# AKS.net
KiCad netlist of a schematic drawn in Altium Designer
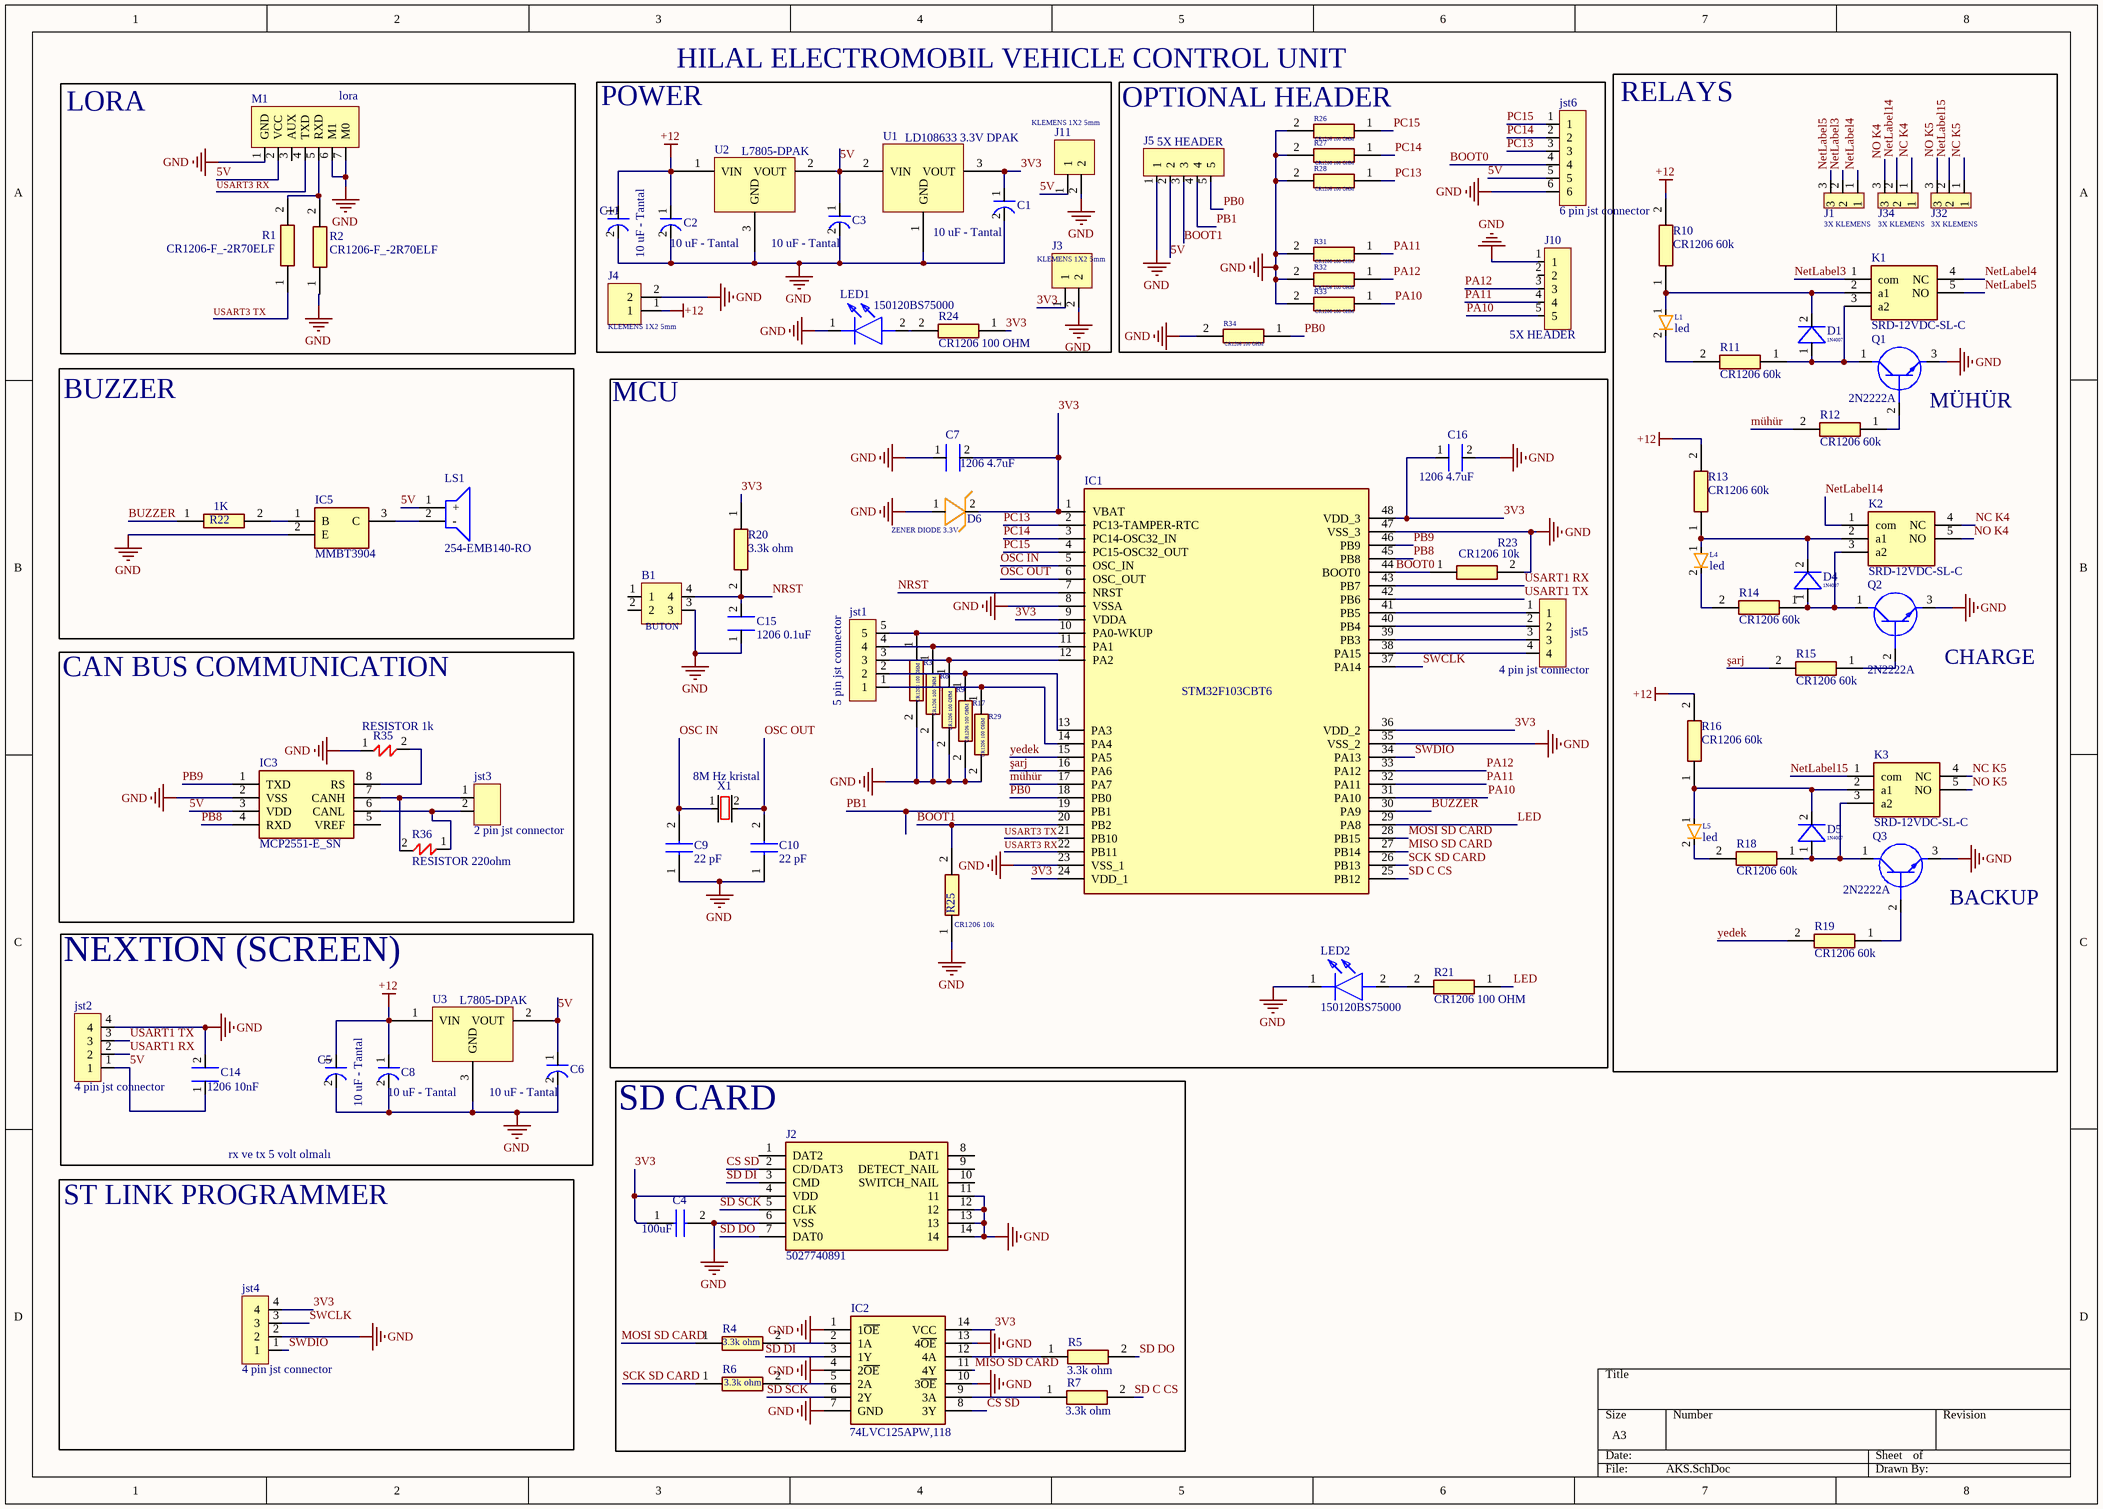
[diagram p0: AKS.SchDoc]

(export (version "E")
  (design (tool "Eeschema 10.0.6"))
  (components
    (comp (ref "B1") (value "BUTON") (footprint "BUTON") (libsource (lib "Schlib1") (part "BUTON")))
    (comp (ref "C1")
      (value "10 uF - Tantal")
      (footprint "C1206-TANT")
      (libsource (lib "Schlib1") (part "10 uF - Tantal"))
    )
    (comp (ref "C2")
      (value "10 uF - Tantal")
      (footprint "C1206-TANT")
      (libsource (lib "Schlib1") (part "10 uF - Tantal"))
    )
    (comp (ref "C3")
      (value "10 uF - Tantal")
      (footprint "C1206-TANT")
      (libsource (lib "Schlib1") (part "10 uF - Tantal"))
    )
    (comp (ref "C4")
      (value "100uF")
      (footprint "PcbLib1:CAPC2012X94N")
      (description "Capacitor")
      (fields
        (field (name "MANUFACTURER_PART_NUMBER") "08055A150JAT2A")
        (field (name "MOUSER PART NUMBER") "581-08055A150J")
      )
      (libsource (lib "*") (part "08055A150JAT2A"))
    )
    (comp (ref "C5")
      (value "10 uF - Tantal")
      (footprint "C1206-TANT")
      (libsource (lib "Schlib1") (part "10 uF - Tantal"))
    )
    (comp (ref "C6")
      (value "10 uF - Tantal")
      (footprint "C1206-TANT")
      (libsource (lib "Schlib1") (part "10 uF - Tantal"))
    )
    (comp (ref "C7")
      (value "1206 4.7uF")
      (footprint "C1206")
      (description "10 uF C1206")
      (libsource (lib "Schlib1") (part "10 uF C1206"))
    )
    (comp (ref "C8")
      (value "10 uF - Tantal")
      (footprint "C1206-TANT")
      (libsource (lib "Schlib1") (part "10 uF - Tantal"))
    )
    (comp (ref "C9")
      (value "22 pF")
      (footprint "PcbLib1:CAPC2012X94N")
      (description "Capacitor")
      (fields
        (field (name "MANUFACTURER_PART_NUMBER") "08055A150JAT2A")
        (field (name "MOUSER PART NUMBER") "581-08055A150J")
      )
      (libsource (lib "*") (part "08055A150JAT2A"))
    )
    (comp (ref "C10")
      (value "22 pF")
      (footprint "PcbLib1:CAPC2012X94N")
      (description "Capacitor")
      (fields
        (field (name "MANUFACTURER_PART_NUMBER") "08055A150JAT2A")
        (field (name "MOUSER PART NUMBER") "581-08055A150J")
      )
      (libsource (lib "*") (part "08055A150JAT2A"))
    )
    (comp (ref "C11")
      (value "10 uF - Tantal")
      (footprint "C1206-TANT")
      (libsource (lib "Schlib1") (part "10 uF - Tantal"))
    )
    (comp (ref "C14")
      (value "1206 10nF")
      (footprint "C1206")
      (description "10 uF C1206")
      (libsource (lib "Schlib1") (part "10 uF C1206"))
    )
    (comp (ref "C15")
      (value "1206 0.1uF")
      (footprint "C1206")
      (description "10 uF C1206")
      (libsource (lib "Schlib1") (part "10 uF C1206"))
    )
    (comp (ref "C16")
      (value "1206 4.7uF")
      (footprint "C1206")
      (description "10 uF C1206")
      (libsource (lib "Schlib1") (part "10 uF C1206"))
    )
    (comp (ref "D1")
      (value "1N4007")
      (footprint "SF-26 DIODE")
      (description "DIODE")
      (libsource (lib "Schlib1") (part "SF-26 DIODE"))
    )
    (comp (ref "D4")
      (value "1N4007")
      (footprint "SF-26 DIODE")
      (description "DIODE")
      (libsource (lib "Schlib1") (part "SF-26 DIODE"))
    )
    (comp (ref "D5")
      (value "1N4007")
      (footprint "SF-26 DIODE")
      (description "DIODE")
      (libsource (lib "Schlib1") (part "SF-26 DIODE"))
    )
    (comp (ref "D6")
      (value "ZENER DIODE 3.3V")
      (footprint "3.3 VOLT ZENER")
      (description "ZENER DIODE")
      (libsource (lib "Schlib1") (part "ZENER DIODE 3.3V"))
    )
    (comp (ref "IC1")
      (value "STM32F103CBT6")
      (footprint "PcbLib1:QFP50P900X900X160-48N")
      (description "Integrated Circuit")
      (fields (field (name "MOUSER PART NUMBER") "511-STM32F103CBT6"))
      (libsource (lib "Schlib1") (part "STM32F103CBT6"))
    )
    (comp (ref "IC2")
      (value "74LVC125APW,118")
      (footprint "PcbLib1:SOP65P640X110-14N")
      (description "Integrated Circuit")
      (fields (field (name "MOUSER PART NUMBER") "771-74LVC125APW-T"))
      (libsource (lib "*") (part "74LVC125APW,118"))
    )
    (comp (ref "IC3")
      (value "MCP2551-E_SN")
      (footprint "PcbLib1:SOIC127P600X175-8N")
      (description "Integrated Circuit")
      (fields
        (field (name "MANUFACTURER_PART_NUMBER") "MCP2551-E/SN")
        (field (name "MOUSER PART NUMBER") "579-MCP2551-E/SN")
      )
      (libsource (lib "Schlib1") (part "MCP2551-E_SN"))
    )
    (comp (ref "IC5")
      (value "MMBT3904")
      (footprint "PcbLib1:SOT95P240X120-3N")
      (description "Integrated Circuit")
      (fields (field (name "MOUSER PART NUMBER") "637-MMBT3904"))
      (libsource (lib "*") (part "MMBT3904"))
    )
    (comp (ref "J1")
      (value "3X KLEMENS")
      (footprint "3x klemens 5mm")
      (libsource (lib "Schlib1") (part "3X KLEMENS"))
    )
    (comp (ref "J2")
      (value "5027740891")
      (footprint "PcbLib1:5027740891")
      (description "Connector")
      (libsource (lib "*") (part "5027740891"))
    )
    (comp (ref "J3")
      (value "KLEMENS 1X2 5mm")
      (footprint "KLEMENS 1x2 - 5mm")
      (description "KLEMENS")
      (libsource (lib "Schlib1") (part "KLEMENS 1X2 3.5mm"))
    )
    (comp (ref "J4")
      (value "KLEMENS 1X2 5mm")
      (footprint "KLEMENS 1x2 - 5mm")
      (description "KLEMENS")
      (libsource (lib "") (part "KLEMENS 1X2 3.5mm_1"))
    )
    (comp (ref "J5") (value "5X HEADER") (footprint "5X HEADER") (libsource (lib "") (part "5X HEADER_1")))
    (comp (ref "J10")
      (value "5X HEADER")
      (footprint "5X HEADER")
      (libsource (lib "Schlib1") (part "5X HEADER"))
    )
    (comp (ref "J11")
      (value "KLEMENS 1X2 5mm")
      (footprint "KLEMENS 1x2 - 5mm")
      (description "KLEMENS")
      (libsource (lib "Schlib1") (part "KLEMENS 1X2 3.5mm"))
    )
    (comp (ref "J32")
      (value "3X KLEMENS")
      (footprint "3x klemens 5mm")
      (libsource (lib "Schlib1") (part "3X KLEMENS"))
    )
    (comp (ref "J34")
      (value "3X KLEMENS")
      (footprint "3x klemens 5mm")
      (libsource (lib "Schlib1") (part "3X KLEMENS"))
    )
    (comp (ref "jst1")
      (value "5 pin jst connector")
      (footprint "5 pin jst")
      (libsource (lib "Schlib1") (part "5 pin jst connector"))
    )
    (comp (ref "jst2")
      (value "4 pin jst connector")
      (footprint "4pin-jst")
      (libsource (lib "") (part "4 pin jst connector_1"))
    )
    (comp (ref "jst3")
      (value "2 pin jst connector")
      (footprint "2 pin jst connector")
      (libsource (lib "Schlib1") (part "2 pin jst connector"))
    )
    (comp (ref "jst4")
      (value "4 pin jst connector")
      (footprint "4pin-jst")
      (libsource (lib "") (part "4 pin jst connector_1"))
    )
    (comp (ref "jst5")
      (value "4 pin jst connector")
      (footprint "4pin-jst")
      (libsource (lib "Schlib1") (part "4 pin jst connector"))
    )
    (comp (ref "jst6")
      (value "6 pin jst connector")
      (footprint "6 pin jst connecttor")
      (description "connector")
      (libsource (lib "Schlib1") (part "6 pin jst connector"))
    )
    (comp (ref "K1")
      (value "SRD-12VDC-SL-C")
      (footprint "RELAY")
      (description "Relay or Contactor")
      (libsource (lib "Schlib1") (part "SRD-12VDC-SL-C"))
    )
    (comp (ref "K2")
      (value "SRD-12VDC-SL-C")
      (footprint "RELAY")
      (description "Relay or Contactor")
      (libsource (lib "Schlib1") (part "SRD-12VDC-SL-C"))
    )
    (comp (ref "K3")
      (value "SRD-12VDC-SL-C")
      (footprint "RELAY")
      (description "Relay or Contactor")
      (libsource (lib "Schlib1") (part "SRD-12VDC-SL-C"))
    )
    (comp (ref "L1") (value "led") (footprint "led") (libsource (lib "Schlib1") (part "led")))
    (comp (ref "L4") (value "led") (footprint "led") (libsource (lib "Schlib1") (part "led")))
    (comp (ref "L5") (value "led") (footprint "led") (libsource (lib "Schlib1") (part "led")))
    (comp (ref "LED1")
      (value "150120BS75000")
      (footprint "PcbLib1:LEDC3214X78N")
      (description "LED")
      (fields (field (name "MOUSER PART NUMBER") "710-150120BS75000"))
      (libsource (lib "Schlib1") (part "150120BS75000"))
    )
    (comp (ref "LED2")
      (value "150120BS75000")
      (footprint "PcbLib1:LEDC3214X78N")
      (description "LED")
      (fields (field (name "MOUSER PART NUMBER") "710-150120BS75000"))
      (libsource (lib "Schlib1") (part "150120BS75000"))
    )
    (comp (ref "LS1")
      (value "254-EMB140-RO")
      (footprint "PcbLib1:254EMB140RO")
      (description "Loudspeaker or Buzzer")
      (libsource (lib "*") (part "254-EMB140-RO"))
    )
    (comp (ref "M1") (value "lora") (footprint "LORA") (libsource (lib "Schlib1") (part "lora")))
    (comp (ref "Q1")
      (value "2N2222A")
      (footprint "PcbLib1:2N2222A")
      (description "Transistor BJT NPN")
      (libsource (lib "Schlib1") (part "2N2222A"))
    )
    (comp (ref "Q2")
      (value "2N2222A")
      (footprint "PcbLib1:2N2222A")
      (description "Transistor BJT NPN")
      (libsource (lib "Schlib1") (part "2N2222A"))
    )
    (comp (ref "Q3")
      (value "2N2222A")
      (footprint "PcbLib1:2N2222A")
      (description "Transistor BJT NPN")
      (libsource (lib "Schlib1") (part "2N2222A"))
    )
    (comp (ref "R1")
      (value "CR1206-F_-2R70ELF")
      (footprint "PcbLib1:RESC3216X75N")
      (description "Resistor")
      (fields
        (field (name "MANUFACTURER_PART_NUMBER") "CR1206-F/-2R70ELF")
        (field (name "MOUSER PART NUMBER") "652-CR1206-F/2R70ELF")
      )
      (libsource (lib "Schlib1") (part "CR1206-F_-2R70ELF"))
    )
    (comp (ref "R2")
      (value "CR1206-F_-2R70ELF")
      (footprint "PcbLib1:RESC3216X75N")
      (description "Resistor")
      (fields
        (field (name "MANUFACTURER_PART_NUMBER") "CR1206-F/-2R70ELF")
        (field (name "MOUSER PART NUMBER") "652-CR1206-F/2R70ELF")
      )
      (libsource (lib "Schlib1") (part "CR1206-F_-2R70ELF"))
    )
    (comp (ref "R3")
      (value "CR1206 100 OHM")
      (footprint "PcbLib1:RESC3216X75N")
      (description "Resistor")
      (fields
        (field (name "MANUFACTURER_PART_NUMBER") "CR1206-F/-2R70ELF")
        (field (name "MOUSER PART NUMBER") "652-CR1206-F/2R70ELF")
      )
      (libsource (lib "") (part "CR1206-F_-2R70ELF_1"))
    )
    (comp (ref "R4")
      (value "3.3k ohm")
      (footprint "PcbLib1:RESC2012X65N")
      (description "Resistor")
      (fields
        (field (name "MANUFACTURER_PART_NUMBER") "CPF0805B100RE1")
        (field (name "MOUSER PART NUMBER") "279-CPF0805B100RE1")
      )
      (libsource (lib "*") (part "CPF0805B100RE1"))
    )
    (comp (ref "R5")
      (value "3.3k ohm")
      (footprint "PcbLib1:RESC2012X65N")
      (description "Resistor")
      (fields
        (field (name "MANUFACTURER_PART_NUMBER") "CPF0805B100RE1")
        (field (name "MOUSER PART NUMBER") "279-CPF0805B100RE1")
      )
      (libsource (lib "*") (part "CPF0805B100RE1"))
    )
    (comp (ref "R6")
      (value "3.3k ohm")
      (footprint "PcbLib1:RESC2012X65N")
      (description "Resistor")
      (fields
        (field (name "MANUFACTURER_PART_NUMBER") "CPF0805B100RE1")
        (field (name "MOUSER PART NUMBER") "279-CPF0805B100RE1")
      )
      (libsource (lib "*") (part "CPF0805B100RE1"))
    )
    (comp (ref "R7")
      (value "3.3k ohm")
      (footprint "PcbLib1:RESC2012X65N")
      (description "Resistor")
      (fields
        (field (name "MANUFACTURER_PART_NUMBER") "CPF0805B100RE1")
        (field (name "MOUSER PART NUMBER") "279-CPF0805B100RE1")
      )
      (libsource (lib "*") (part "CPF0805B100RE1"))
    )
    (comp (ref "R8")
      (value "CR1206 100 OHM")
      (footprint "PcbLib1:RESC3216X75N")
      (description "Resistor")
      (fields
        (field (name "MANUFACTURER_PART_NUMBER") "CR1206-F/-2R70ELF")
        (field (name "MOUSER PART NUMBER") "652-CR1206-F/2R70ELF")
      )
      (libsource (lib "") (part "CR1206-F_-2R70ELF_1"))
    )
    (comp (ref "R9")
      (value "CR1206 100 OHM")
      (footprint "PcbLib1:RESC3216X75N")
      (description "Resistor")
      (fields
        (field (name "MANUFACTURER_PART_NUMBER") "CR1206-F/-2R70ELF")
        (field (name "MOUSER PART NUMBER") "652-CR1206-F/2R70ELF")
      )
      (libsource (lib "") (part "CR1206-F_-2R70ELF_1"))
    )
    (comp (ref "R10")
      (value "CR1206 60k")
      (footprint "PcbLib1:RESC3216X75N")
      (description "Resistor")
      (fields
        (field (name "MANUFACTURER_PART_NUMBER") "CR1206-F/-2R70ELF")
        (field (name "MOUSER PART NUMBER") "652-CR1206-F/2R70ELF")
      )
      (libsource (lib "") (part "CR1206-F_-2R70ELF_2"))
    )
    (comp (ref "R11")
      (value "CR1206 60k")
      (footprint "PcbLib1:RESC3216X75N")
      (description "Resistor")
      (fields
        (field (name "MANUFACTURER_PART_NUMBER") "CR1206-F/-2R70ELF")
        (field (name "MOUSER PART NUMBER") "652-CR1206-F/2R70ELF")
      )
      (libsource (lib "*") (part "CR1206-F_-2R70ELF"))
    )
    (comp (ref "R12")
      (value "CR1206 60k")
      (footprint "PcbLib1:RESC3216X75N")
      (description "Resistor")
      (fields
        (field (name "MANUFACTURER_PART_NUMBER") "CR1206-F/-2R70ELF")
        (field (name "MOUSER PART NUMBER") "652-CR1206-F/2R70ELF")
      )
      (libsource (lib "*") (part "CR1206-F_-2R70ELF"))
    )
    (comp (ref "R13")
      (value "CR1206 60k")
      (footprint "PcbLib1:RESC3216X75N")
      (description "Resistor")
      (fields
        (field (name "MANUFACTURER_PART_NUMBER") "CR1206-F/-2R70ELF")
        (field (name "MOUSER PART NUMBER") "652-CR1206-F/2R70ELF")
      )
      (libsource (lib "") (part "CR1206-F_-2R70ELF_2"))
    )
    (comp (ref "R14")
      (value "CR1206 60k")
      (footprint "PcbLib1:RESC3216X75N")
      (description "Resistor")
      (fields
        (field (name "MANUFACTURER_PART_NUMBER") "CR1206-F/-2R70ELF")
        (field (name "MOUSER PART NUMBER") "652-CR1206-F/2R70ELF")
      )
      (libsource (lib "*") (part "CR1206-F_-2R70ELF"))
    )
    (comp (ref "R15")
      (value "CR1206 60k")
      (footprint "PcbLib1:RESC3216X75N")
      (description "Resistor")
      (fields
        (field (name "MANUFACTURER_PART_NUMBER") "CR1206-F/-2R70ELF")
        (field (name "MOUSER PART NUMBER") "652-CR1206-F/2R70ELF")
      )
      (libsource (lib "*") (part "CR1206-F_-2R70ELF"))
    )
    (comp (ref "R16")
      (value "CR1206 60k")
      (footprint "PcbLib1:RESC3216X75N")
      (description "Resistor")
      (fields
        (field (name "MANUFACTURER_PART_NUMBER") "CR1206-F/-2R70ELF")
        (field (name "MOUSER PART NUMBER") "652-CR1206-F/2R70ELF")
      )
      (libsource (lib "") (part "CR1206-F_-2R70ELF_2"))
    )
    (comp (ref "R17")
      (value "CR1206 100 OHM")
      (footprint "PcbLib1:RESC3216X75N")
      (description "Resistor")
      (fields
        (field (name "MANUFACTURER_PART_NUMBER") "CR1206-F/-2R70ELF")
        (field (name "MOUSER PART NUMBER") "652-CR1206-F/2R70ELF")
      )
      (libsource (lib "") (part "CR1206-F_-2R70ELF_1"))
    )
    (comp (ref "R18")
      (value "CR1206 60k")
      (footprint "PcbLib1:RESC3216X75N")
      (description "Resistor")
      (fields
        (field (name "MANUFACTURER_PART_NUMBER") "CR1206-F/-2R70ELF")
        (field (name "MOUSER PART NUMBER") "652-CR1206-F/2R70ELF")
      )
      (libsource (lib "*") (part "CR1206-F_-2R70ELF"))
    )
    (comp (ref "R19")
      (value "CR1206 60k")
      (footprint "PcbLib1:RESC3216X75N")
      (description "Resistor")
      (fields
        (field (name "MANUFACTURER_PART_NUMBER") "CR1206-F/-2R70ELF")
        (field (name "MOUSER PART NUMBER") "652-CR1206-F/2R70ELF")
      )
      (libsource (lib "*") (part "CR1206-F_-2R70ELF"))
    )
    (comp (ref "R20")
      (value "3.3k ohm")
      (footprint "PcbLib1:RESC2012X65N")
      (description "Resistor")
      (fields
        (field (name "MANUFACTURER_PART_NUMBER") "CPF0805B100RE1")
        (field (name "MOUSER PART NUMBER") "279-CPF0805B100RE1")
      )
      (libsource (lib "") (part "CPF0805B100RE1_1"))
    )
    (comp (ref "R21")
      (value "CR1206 100 OHM")
      (footprint "PcbLib1:RESC3216X75N")
      (description "Resistor")
      (fields
        (field (name "MANUFACTURER_PART_NUMBER") "CR1206-F/-2R70ELF")
        (field (name "MOUSER PART NUMBER") "652-CR1206-F/2R70ELF")
      )
      (libsource (lib "*") (part "CR1206-F_-2R70ELF"))
    )
    (comp (ref "R22")
      (value "1K")
      (footprint "PcbLib1:RESC2012X65N")
      (description "Resistor")
      (fields
        (field (name "MANUFACTURER_PART_NUMBER") "CPF0805B100RE1")
        (field (name "MOUSER PART NUMBER") "279-CPF0805B100RE1")
      )
      (libsource (lib "*") (part "CPF0805B100RE1"))
    )
    (comp (ref "R23")
      (value "CR1206 10k")
      (footprint "PcbLib1:RESC3216X75N")
      (description "Resistor")
      (fields
        (field (name "MANUFACTURER_PART_NUMBER") "CR1206-F/-2R70ELF")
        (field (name "MOUSER PART NUMBER") "652-CR1206-F/2R70ELF")
      )
      (libsource (lib "") (part "CR1206-F_-2R70ELF_3"))
    )
    (comp (ref "R24")
      (value "CR1206 100 OHM")
      (footprint "PcbLib1:RESC3216X75N")
      (description "Resistor")
      (fields
        (field (name "MANUFACTURER_PART_NUMBER") "CR1206-F/-2R70ELF")
        (field (name "MOUSER PART NUMBER") "652-CR1206-F/2R70ELF")
      )
      (libsource (lib "*") (part "CR1206-F_-2R70ELF"))
    )
    (comp (ref "R25")
      (value "CR1206 10k")
      (footprint "PcbLib1:RESC3216X75N")
      (description "Resistor")
      (fields
        (field (name "MANUFACTURER_PART_NUMBER") "CR1206-F/-2R70ELF")
        (field (name "MOUSER PART NUMBER") "652-CR1206-F/2R70ELF")
      )
      (libsource (lib "") (part "CR1206-F_-2R70ELF_2"))
    )
    (comp (ref "R26")
      (value "CR1206 100 OHM")
      (footprint "PcbLib1:RESC3216X75N")
      (description "Resistor")
      (fields
        (field (name "MANUFACTURER_PART_NUMBER") "CR1206-F/-2R70ELF")
        (field (name "MOUSER PART NUMBER") "652-CR1206-F/2R70ELF")
      )
      (libsource (lib "*") (part "CR1206-F_-2R70ELF"))
    )
    (comp (ref "R27")
      (value "CR1206 100 OHM")
      (footprint "PcbLib1:RESC3216X75N")
      (description "Resistor")
      (fields
        (field (name "MANUFACTURER_PART_NUMBER") "CR1206-F/-2R70ELF")
        (field (name "MOUSER PART NUMBER") "652-CR1206-F/2R70ELF")
      )
      (libsource (lib "*") (part "CR1206-F_-2R70ELF"))
    )
    (comp (ref "R28")
      (value "CR1206 100 OHM")
      (footprint "PcbLib1:RESC3216X75N")
      (description "Resistor")
      (fields
        (field (name "MANUFACTURER_PART_NUMBER") "CR1206-F/-2R70ELF")
        (field (name "MOUSER PART NUMBER") "652-CR1206-F/2R70ELF")
      )
      (libsource (lib "*") (part "CR1206-F_-2R70ELF"))
    )
    (comp (ref "R29")
      (value "CR1206 100 OHM")
      (footprint "PcbLib1:RESC3216X75N")
      (description "Resistor")
      (fields
        (field (name "MANUFACTURER_PART_NUMBER") "CR1206-F/-2R70ELF")
        (field (name "MOUSER PART NUMBER") "652-CR1206-F/2R70ELF")
      )
      (libsource (lib "") (part "CR1206-F_-2R70ELF_1"))
    )
    (comp (ref "R31")
      (value "CR1206 100 OHM")
      (footprint "PcbLib1:RESC3216X75N")
      (description "Resistor")
      (fields
        (field (name "MANUFACTURER_PART_NUMBER") "CR1206-F/-2R70ELF")
        (field (name "MOUSER PART NUMBER") "652-CR1206-F/2R70ELF")
      )
      (libsource (lib "*") (part "CR1206-F_-2R70ELF"))
    )
    (comp (ref "R32")
      (value "CR1206 100 OHM")
      (footprint "PcbLib1:RESC3216X75N")
      (description "Resistor")
      (fields
        (field (name "MANUFACTURER_PART_NUMBER") "CR1206-F/-2R70ELF")
        (field (name "MOUSER PART NUMBER") "652-CR1206-F/2R70ELF")
      )
      (libsource (lib "*") (part "CR1206-F_-2R70ELF"))
    )
    (comp (ref "R33")
      (value "CR1206 100 OHM")
      (footprint "PcbLib1:RESC3216X75N")
      (description "Resistor")
      (fields
        (field (name "MANUFACTURER_PART_NUMBER") "CR1206-F/-2R70ELF")
        (field (name "MOUSER PART NUMBER") "652-CR1206-F/2R70ELF")
      )
      (libsource (lib "*") (part "CR1206-F_-2R70ELF"))
    )
    (comp (ref "R34")
      (value "CR1206 100 OHM")
      (footprint "PcbLib1:RESC3216X75N")
      (description "Resistor")
      (fields
        (field (name "MANUFACTURER_PART_NUMBER") "CR1206-F/-2R70ELF")
        (field (name "MOUSER PART NUMBER") "652-CR1206-F/2R70ELF")
      )
      (libsource (lib "*") (part "CR1206-F_-2R70ELF"))
    )
    (comp (ref "R35")
      (value "RESISTOR 1k")
      (footprint "GENERAL RESISTOR")
      (description "GENERAL TYPE THT RES")
      (libsource (lib "Schlib1") (part "RESISTOR"))
    )
    (comp (ref "R36")
      (value "RESISTOR 220ohm")
      (footprint "GENERAL RESISTOR")
      (description "GENERAL TYPE THT RES")
      (libsource (lib "Schlib1") (part "RESISTOR"))
    )
    (comp (ref "U1")
      (value "LD108633 3.3V DPAK")
      (footprint "DPAK228P972X240-3N")
      (description "LD108633 3.3V REGULATOR")
      (libsource (lib "Schlib1") (part "LD108633 3.3V DPAK"))
    )
    (comp (ref "U2")
      (value "L7805-DPAK")
      (footprint "DPAK228P972X240-3N")
      (description "L7805 5V REGULATOR. SMD PAKET")
      (libsource (lib "Schlib1") (part "L7805-DPAK"))
    )
    (comp (ref "U3")
      (value "L7805-DPAK")
      (footprint "DPAK228P972X240-3N")
      (description "L7805 5V REGULATOR. SMD PAKET")
      (libsource (lib "Schlib1") (part "L7805-DPAK"))
    )
    (comp (ref "X1")
      (value "8M Hz kristal")
      (footprint "8M Hz kristal")
      (libsource (lib "Schlib1") (part "8M Hz kristal"))
    )
  )
  (nets
    (net (code "1") (name "+12") (class "Default")
      (node (ref "C11") (pin "1") (pinfunction "1_1") (pintype "passive"))
      (node (ref "C2") (pin "1") (pinfunction "1_1") (pintype "passive"))
      (node (ref "C5") (pin "1") (pinfunction "1_1") (pintype "passive"))
      (node (ref "C8") (pin "1") (pinfunction "1_1") (pintype "passive"))
      (node (ref "J4") (pin "1") (pinfunction "1_1") (pintype "passive"))
      (node (ref "R10") (pin "2") (pinfunction "2_2") (pintype "passive"))
      (node (ref "R13") (pin "2") (pinfunction "2_2") (pintype "passive"))
      (node (ref "R16") (pin "2") (pinfunction "2_2") (pintype "passive"))
      (node (ref "U2") (pin "1") (pinfunction "VIN_1") (pintype "passive"))
      (node (ref "U3") (pin "1") (pinfunction "VIN_1") (pintype "passive"))
    )
    (net (code "2") (name "/3V3") (class "Default")
      (node (ref "C1") (pin "1") (pinfunction "1_1") (pintype "passive"))
      (node (ref "C16") (pin "1") (pinfunction "1_1") (pintype "passive"))
      (node (ref "C4") (pin "1") (pinfunction "1_1") (pintype "passive"))
      (node (ref "C7") (pin "2") (pinfunction "2_2") (pintype "passive"))
      (node (ref "D6") (pin "2") (pinfunction "2_2") (pintype "passive"))
      (node (ref "IC1") (pin "1") (pinfunction "VBAT_1") (pintype "passive"))
      (node (ref "IC1") (pin "24") (pinfunction "VDD_1_24") (pintype "passive"))
      (node (ref "IC1") (pin "36") (pinfunction "VDD_2_36") (pintype "passive"))
      (node (ref "IC1") (pin "48") (pinfunction "VDD_3_48") (pintype "passive"))
      (node (ref "IC1") (pin "9") (pinfunction "VDDA_9") (pintype "passive"))
      (node (ref "IC2") (pin "14") (pinfunction "VCC_14") (pintype "passive"))
      (node (ref "J2") (pin "4") (pinfunction "VDD_4") (pintype "passive"))
      (node (ref "J3") (pin "1") (pinfunction "1_1") (pintype "passive"))
      (node (ref "R20") (pin "1") (pinfunction "1_1") (pintype "passive"))
      (node (ref "R24") (pin "1") (pinfunction "1_1") (pintype "passive"))
      (node (ref "U1") (pin "3") (pinfunction "VOUT_3") (pintype "passive"))
      (node (ref "jst4") (pin "4") (pinfunction "4_4") (pintype "passive"))
    )
    (net (code "3") (name "/5V") (class "Default")
      (node (ref "C14") (pin "1") (pinfunction "1_1") (pintype "passive"))
      (node (ref "C3") (pin "1") (pinfunction "1_1") (pintype "passive"))
      (node (ref "C6") (pin "1") (pinfunction "1_1") (pintype "passive"))
      (node (ref "IC3") (pin "3") (pinfunction "VDD_3") (pintype "passive"))
      (node (ref "J11") (pin "1") (pinfunction "1_1") (pintype "passive"))
      (node (ref "J5") (pin "2") (pinfunction "2_2") (pintype "passive"))
      (node (ref "LS1") (pin "1") (pinfunction "+_1") (pintype "passive"))
      (node (ref "M1") (pin "2") (pinfunction "VCC_2") (pintype "passive"))
      (node (ref "U1") (pin "2") (pinfunction "VIN_2") (pintype "passive"))
      (node (ref "U2") (pin "2") (pinfunction "VOUT_2") (pintype "passive"))
      (node (ref "U3") (pin "2") (pinfunction "VOUT_2") (pintype "passive"))
      (node (ref "jst2") (pin "1") (pinfunction "1_1") (pintype "passive"))
      (node (ref "jst6") (pin "5") (pinfunction "5_5") (pintype "passive"))
    )
    (net (code "4") (name "/BOOT0") (class "Default")
      (node (ref "IC1") (pin "44") (pinfunction "BOOT0_44") (pintype "passive"))
      (node (ref "R23") (pin "1") (pinfunction "1_1") (pintype "passive"))
      (node (ref "jst6") (pin "4") (pinfunction "4_4") (pintype "passive"))
    )
    (net (code "5") (name "/BOOT1") (class "Default")
      (node (ref "IC1") (pin "20") (pinfunction "PB2_20") (pintype "passive"))
      (node (ref "J5") (pin "3") (pinfunction "3_3") (pintype "passive"))
      (node (ref "R25") (pin "2") (pinfunction "2_2") (pintype "passive"))
    )
    (net (code "6") (name "/BUZZER") (class "Default")
      (node (ref "IC1") (pin "30") (pinfunction "PA9_30") (pintype "passive"))
      (node (ref "R22") (pin "1") (pinfunction "1_1") (pintype "passive"))
    )
    (net (code "7") (name "/CS SD") (class "Default")
      (node (ref "IC2") (pin "8") (pinfunction "3Y_8") (pintype "passive"))
      (node (ref "J2") (pin "2") (pinfunction "CD/DAT3_2") (pintype "passive"))
    )
    (net (code "8") (name "/LED") (class "Default")
      (node (ref "IC1") (pin "29") (pinfunction "PA8_29") (pintype "passive"))
      (node (ref "R21") (pin "1") (pinfunction "1_1") (pintype "passive"))
    )
    (net (code "9") (name "/MISO SD CARD") (class "Default")
      (node (ref "IC1") (pin "27") (pinfunction "PB14_27") (pintype "passive"))
      (node (ref "IC2") (pin "11") (pinfunction "4Y_11") (pintype "passive"))
    )
    (net (code "10") (name "/MOSI SD CARD") (class "Default")
      (node (ref "IC1") (pin "28") (pinfunction "PB15_28") (pintype "passive"))
      (node (ref "R4") (pin "1") (pinfunction "1_1") (pintype "passive"))
    )
    (net (code "11") (name "/NC K4") (class "Default")
      (node (ref "J34") (pin "1") (pinfunction "1_1") (pintype "passive"))
      (node (ref "K2") (pin "4") (pinfunction "NC_4") (pintype "passive"))
    )
    (net (code "12") (name "/NC K5") (class "Default")
      (node (ref "J32") (pin "1") (pinfunction "1_1") (pintype "passive"))
      (node (ref "K3") (pin "4") (pinfunction "NC_4") (pintype "passive"))
    )
    (net (code "13") (name "/NO K4") (class "Default")
      (node (ref "J34") (pin "3") (pinfunction "3_3") (pintype "passive"))
      (node (ref "K2") (pin "5") (pinfunction "NO_5") (pintype "passive"))
    )
    (net (code "14") (name "/NO K5") (class "Default")
      (node (ref "J32") (pin "3") (pinfunction "3_3") (pintype "passive"))
      (node (ref "K3") (pin "5") (pinfunction "NO_5") (pintype "passive"))
    )
    (net (code "15") (name "/NRST") (class "Default")
      (node (ref "B1") (pin "4") (pinfunction "4_4") (pintype "passive"))
      (node (ref "C15") (pin "2") (pinfunction "2_2") (pintype "passive"))
      (node (ref "IC1") (pin "7") (pinfunction "NRST_7") (pintype "passive"))
      (node (ref "R20") (pin "2") (pinfunction "2_2") (pintype "passive"))
    )
    (net (code "16") (name "/NetLabel3") (class "Default")
      (node (ref "J1") (pin "2") (pinfunction "2_2") (pintype "passive"))
      (node (ref "K1") (pin "1") (pinfunction "com_1") (pintype "passive"))
    )
    (net (code "17") (name "/NetLabel4") (class "Default")
      (node (ref "J1") (pin "1") (pinfunction "1_1") (pintype "passive"))
      (node (ref "K1") (pin "4") (pinfunction "NC_4") (pintype "passive"))
    )
    (net (code "18") (name "/NetLabel5") (class "Default")
      (node (ref "J1") (pin "3") (pinfunction "3_3") (pintype "passive"))
      (node (ref "K1") (pin "5") (pinfunction "NO_5") (pintype "passive"))
    )
    (net (code "19") (name "/NetLabel14") (class "Default")
      (node (ref "J34") (pin "2") (pinfunction "2_2") (pintype "passive"))
      (node (ref "K2") (pin "1") (pinfunction "com_1") (pintype "passive"))
    )
    (net (code "20") (name "/NetLabel15") (class "Default")
      (node (ref "J32") (pin "2") (pinfunction "2_2") (pintype "passive"))
      (node (ref "K3") (pin "1") (pinfunction "com_1") (pintype "passive"))
    )
    (net (code "21") (name "/OSC IN") (class "Default")
      (node (ref "C9") (pin "2") (pinfunction "2_2") (pintype "passive"))
      (node (ref "IC1") (pin "5") (pinfunction "OSC_IN_5") (pintype "passive"))
      (node (ref "X1") (pin "1") (pinfunction "1_1") (pintype "passive"))
    )
    (net (code "22") (name "/OSC OUT") (class "Default")
      (node (ref "C10") (pin "2") (pinfunction "2_2") (pintype "passive"))
      (node (ref "IC1") (pin "6") (pinfunction "OSC_OUT_6") (pintype "passive"))
      (node (ref "X1") (pin "2") (pinfunction "2_2") (pintype "passive"))
    )
    (net (code "23") (name "/PA10") (class "Default")
      (node (ref "IC1") (pin "31") (pinfunction "PA10_31") (pintype "passive"))
      (node (ref "J10") (pin "5") (pinfunction "5_5") (pintype "passive"))
      (node (ref "R33") (pin "1") (pinfunction "1_1") (pintype "passive"))
    )
    (net (code "24") (name "/PA11") (class "Default")
      (node (ref "IC1") (pin "32") (pinfunction "PA11_32") (pintype "passive"))
      (node (ref "J10") (pin "4") (pinfunction "4_4") (pintype "passive"))
      (node (ref "R31") (pin "1") (pinfunction "1_1") (pintype "passive"))
    )
    (net (code "25") (name "/PA12") (class "Default")
      (node (ref "IC1") (pin "33") (pinfunction "PA12_33") (pintype "passive"))
      (node (ref "J10") (pin "3") (pinfunction "3_3") (pintype "passive"))
      (node (ref "R32") (pin "1") (pinfunction "1_1") (pintype "passive"))
    )
    (net (code "26") (name "/PB0") (class "Default")
      (node (ref "IC1") (pin "18") (pinfunction "PB0_18") (pintype "passive"))
      (node (ref "J5") (pin "5") (pinfunction "5_5") (pintype "passive"))
      (node (ref "R34") (pin "1") (pinfunction "1_1") (pintype "passive"))
    )
    (net (code "27") (name "/PB1") (class "Default")
      (node (ref "IC1") (pin "19") (pinfunction "PB1_19") (pintype "passive"))
      (node (ref "J5") (pin "4") (pinfunction "4_4") (pintype "passive"))
    )
    (net (code "28") (name "/PB8") (class "Default")
      (node (ref "IC1") (pin "45") (pinfunction "PB8_45") (pintype "passive"))
      (node (ref "IC3") (pin "4") (pinfunction "RXD_4") (pintype "passive"))
    )
    (net (code "29") (name "/PB9") (class "Default")
      (node (ref "IC1") (pin "46") (pinfunction "PB9_46") (pintype "passive"))
      (node (ref "IC3") (pin "1") (pinfunction "TXD_1") (pintype "passive"))
    )
    (net (code "30") (name "/PC13") (class "Default")
      (node (ref "IC1") (pin "2") (pinfunction "PC13-TAMPER-RTC_2") (pintype "passive"))
      (node (ref "R28") (pin "1") (pinfunction "1_1") (pintype "passive"))
      (node (ref "jst6") (pin "3") (pinfunction "3_3") (pintype "passive"))
    )
    (net (code "31") (name "/PC14") (class "Default")
      (node (ref "IC1") (pin "3") (pinfunction "PC14-OSC32_IN_3") (pintype "passive"))
      (node (ref "R27") (pin "1") (pinfunction "1_1") (pintype "passive"))
      (node (ref "jst6") (pin "2") (pinfunction "2_2") (pintype "passive"))
    )
    (net (code "32") (name "/PC15") (class "Default")
      (node (ref "IC1") (pin "4") (pinfunction "PC15-OSC32_OUT_4") (pintype "passive"))
      (node (ref "R26") (pin "1") (pinfunction "1_1") (pintype "passive"))
      (node (ref "jst6") (pin "1") (pinfunction "1_1") (pintype "passive"))
    )
    (net (code "33") (name "/SCK SD CARD") (class "Default")
      (node (ref "IC1") (pin "26") (pinfunction "PB13_26") (pintype "passive"))
      (node (ref "R6") (pin "1") (pinfunction "1_1") (pintype "passive"))
    )
    (net (code "34") (name "/SD C CS") (class "Default")
      (node (ref "IC1") (pin "25") (pinfunction "PB12_25") (pintype "passive"))
      (node (ref "R7") (pin "2") (pinfunction "2_2") (pintype "passive"))
    )
    (net (code "35") (name "/SD DI") (class "Default")
      (node (ref "IC2") (pin "3") (pinfunction "1Y_3") (pintype "passive"))
      (node (ref "J2") (pin "3") (pinfunction "CMD_3") (pintype "passive"))
    )
    (net (code "36") (name "/SD DO") (class "Default")
      (node (ref "J2") (pin "7") (pinfunction "DAT0_7") (pintype "passive"))
      (node (ref "R5") (pin "2") (pinfunction "2_2") (pintype "passive"))
    )
    (net (code "37") (name "/SD SCK") (class "Default")
      (node (ref "IC2") (pin "6") (pinfunction "2Y_6") (pintype "passive"))
      (node (ref "J2") (pin "5") (pinfunction "CLK_5") (pintype "passive"))
    )
    (net (code "38") (name "/SWCLK") (class "Default")
      (node (ref "IC1") (pin "37") (pinfunction "PA14_37") (pintype "passive"))
      (node (ref "jst4") (pin "3") (pinfunction "3_3") (pintype "passive"))
    )
    (net (code "39") (name "/SWDIO") (class "Default")
      (node (ref "IC1") (pin "34") (pinfunction "PA13_34") (pintype "passive"))
      (node (ref "jst4") (pin "1") (pinfunction "1_1") (pintype "passive"))
    )
    (net (code "40") (name "/USART1 RX") (class "Default")
      (node (ref "IC1") (pin "43") (pinfunction "PB7_43") (pintype "passive"))
      (node (ref "jst2") (pin "2") (pinfunction "2_2") (pintype "passive"))
    )
    (net (code "41") (name "/USART1 TX") (class "Default")
      (node (ref "IC1") (pin "42") (pinfunction "PB6_42") (pintype "passive"))
      (node (ref "jst2") (pin "3") (pinfunction "3_3") (pintype "passive"))
    )
    (net (code "42") (name "/USART3 RX") (class "Default")
      (node (ref "IC1") (pin "22") (pinfunction "PB11_22") (pintype "passive"))
      (node (ref "M1") (pin "4") (pinfunction "TXD_4") (pintype "passive"))
    )
    (net (code "43") (name "/USART3 TX") (class "Default")
      (node (ref "IC1") (pin "21") (pinfunction "PB10_21") (pintype "passive"))
      (node (ref "R1") (pin "1") (pinfunction "1_1") (pintype "passive"))
    )
    (net (code "44") (name "/mühür") (class "Default")
      (node (ref "IC1") (pin "17") (pinfunction "PA7_17") (pintype "passive"))
      (node (ref "R12") (pin "2") (pinfunction "2_2") (pintype "passive"))
    )
    (net (code "45") (name "/yedek") (class "Default")
      (node (ref "IC1") (pin "15") (pinfunction "PA5_15") (pintype "passive"))
      (node (ref "R19") (pin "2") (pinfunction "2_2") (pintype "passive"))
    )
    (net (code "46") (name "/şarj") (class "Default")
      (node (ref "IC1") (pin "16") (pinfunction "PA6_16") (pintype "passive"))
      (node (ref "R15") (pin "2") (pinfunction "2_2") (pintype "passive"))
    )
    (net (code "47") (name "GND") (class "Default")
      (node (ref "B1") (pin "3") (pinfunction "3_3") (pintype "passive"))
      (node (ref "C1") (pin "2") (pinfunction "2_2") (pintype "passive"))
      (node (ref "C10") (pin "1") (pinfunction "1_1") (pintype "passive"))
      (node (ref "C11") (pin "2") (pinfunction "2_2") (pintype "passive"))
      (node (ref "C14") (pin "2") (pinfunction "2_2") (pintype "passive"))
      (node (ref "C15") (pin "1") (pinfunction "1_1") (pintype "passive"))
      (node (ref "C16") (pin "2") (pinfunction "2_2") (pintype "passive"))
      (node (ref "C2") (pin "2") (pinfunction "2_2") (pintype "passive"))
      (node (ref "C3") (pin "2") (pinfunction "2_2") (pintype "passive"))
      (node (ref "C4") (pin "2") (pinfunction "2_2") (pintype "passive"))
      (node (ref "C5") (pin "2") (pinfunction "2_2") (pintype "passive"))
      (node (ref "C6") (pin "2") (pinfunction "2_2") (pintype "passive"))
      (node (ref "C7") (pin "1") (pinfunction "1_1") (pintype "passive"))
      (node (ref "C8") (pin "2") (pinfunction "2_2") (pintype "passive"))
      (node (ref "C9") (pin "1") (pinfunction "1_1") (pintype "passive"))
      (node (ref "D6") (pin "1") (pinfunction "1_1") (pintype "passive"))
      (node (ref "IC1") (pin "23") (pinfunction "VSS_1_23") (pintype "passive"))
      (node (ref "IC1") (pin "35") (pinfunction "VSS_2_35") (pintype "passive"))
      (node (ref "IC1") (pin "47") (pinfunction "VSS_3_47") (pintype "passive"))
      (node (ref "IC1") (pin "8") (pinfunction "VSSA_8") (pintype "passive"))
      (node (ref "IC2") (pin "1") (pinfunction "1~{OE}_1") (pintype "passive"))
      (node (ref "IC2") (pin "10") (pinfunction "3~{OE}_10") (pintype "passive"))
      (node (ref "IC2") (pin "13") (pinfunction "4~{OE}_13") (pintype "passive"))
      (node (ref "IC2") (pin "4") (pinfunction "2~{OE}_4") (pintype "passive"))
      (node (ref "IC2") (pin "7") (pinfunction "GND_7") (pintype "passive"))
      (node (ref "IC3") (pin "2") (pinfunction "VSS_2") (pintype "passive"))
      (node (ref "IC5") (pin "2") (pinfunction "E_2") (pintype "passive"))
      (node (ref "J10") (pin "1") (pinfunction "1_1") (pintype "passive"))
      (node (ref "J11") (pin "2") (pinfunction "2_2") (pintype "passive"))
      (node (ref "J2") (pin "11") (pinfunction "11_11") (pintype "passive"))
      (node (ref "J2") (pin "12") (pinfunction "12_12") (pintype "passive"))
      (node (ref "J2") (pin "13") (pinfunction "13_13") (pintype "passive"))
      (node (ref "J2") (pin "14") (pinfunction "14_14") (pintype "passive"))
      (node (ref "J2") (pin "6") (pinfunction "VSS_6") (pintype "passive"))
      (node (ref "J3") (pin "2") (pinfunction "2_2") (pintype "passive"))
      (node (ref "J4") (pin "2") (pinfunction "2_2") (pintype "passive"))
      (node (ref "J5") (pin "1") (pinfunction "1_1") (pintype "passive"))
      (node (ref "LED1") (pin "1") (pinfunction "K_1") (pintype "passive"))
      (node (ref "LED2") (pin "1") (pinfunction "K_1") (pintype "passive"))
      (node (ref "M1") (pin "1") (pinfunction "GND_1") (pintype "passive"))
      (node (ref "M1") (pin "6") (pinfunction "M1_6") (pintype "passive"))
      (node (ref "M1") (pin "7") (pinfunction "M0_7") (pintype "passive"))
      (node (ref "Q1") (pin "3") (pinfunction "E_3") (pintype "passive"))
      (node (ref "Q2") (pin "3") (pinfunction "E_3") (pintype "passive"))
      (node (ref "Q3") (pin "3") (pinfunction "E_3") (pintype "passive"))
      (node (ref "R17") (pin "2") (pinfunction "2_2") (pintype "passive"))
      (node (ref "R2") (pin "1") (pinfunction "1_1") (pintype "passive"))
      (node (ref "R23") (pin "2") (pinfunction "2_2") (pintype "passive"))
      (node (ref "R25") (pin "1") (pinfunction "1_1") (pintype "passive"))
      (node (ref "R26") (pin "2") (pinfunction "2_2") (pintype "passive"))
      (node (ref "R27") (pin "2") (pinfunction "2_2") (pintype "passive"))
      (node (ref "R28") (pin "2") (pinfunction "2_2") (pintype "passive"))
      (node (ref "R29") (pin "2") (pinfunction "2_2") (pintype "passive"))
      (node (ref "R3") (pin "2") (pinfunction "2_2") (pintype "passive"))
      (node (ref "R31") (pin "2") (pinfunction "2_2") (pintype "passive"))
      (node (ref "R32") (pin "2") (pinfunction "2_2") (pintype "passive"))
      (node (ref "R33") (pin "2") (pinfunction "2_2") (pintype "passive"))
      (node (ref "R34") (pin "2") (pinfunction "2_2") (pintype "passive"))
      (node (ref "R35") (pin "1") (pinfunction "1_1") (pintype "passive"))
      (node (ref "R8") (pin "2") (pinfunction "2_2") (pintype "passive"))
      (node (ref "R9") (pin "2") (pinfunction "2_2") (pintype "passive"))
      (node (ref "U1") (pin "1") (pinfunction "GND_1") (pintype "passive"))
      (node (ref "U2") (pin "3") (pinfunction "GND_3") (pintype "passive"))
      (node (ref "U3") (pin "3") (pinfunction "GND_3") (pintype "passive"))
      (node (ref "jst2") (pin "4") (pinfunction "4_4") (pintype "passive"))
      (node (ref "jst4") (pin "2") (pinfunction "2_2") (pintype "passive"))
      (node (ref "jst6") (pin "6") (pinfunction "6_6") (pintype "passive"))
    )
    (net (code "48") (name "Net-(IC1-PA0-WKUP)") (class "Default")
      (node (ref "IC1") (pin "10") (pinfunction "PA0-WKUP_10") (pintype "passive"))
      (node (ref "R3") (pin "1") (pinfunction "1_1") (pintype "passive"))
      (node (ref "jst1") (pin "5") (pinfunction "5_5") (pintype "passive"))
    )
    (net (code "49") (name "Net-(IC1-PA1)") (class "Default")
      (node (ref "IC1") (pin "11") (pinfunction "PA1_11") (pintype "passive"))
      (node (ref "R8") (pin "1") (pinfunction "1_1") (pintype "passive"))
      (node (ref "jst1") (pin "4") (pinfunction "4_4") (pintype "passive"))
    )
    (net (code "50") (name "Net-(IC1-PA2)") (class "Default")
      (node (ref "IC1") (pin "12") (pinfunction "PA2_12") (pintype "passive"))
      (node (ref "R9") (pin "1") (pinfunction "1_1") (pintype "passive"))
      (node (ref "jst1") (pin "3") (pinfunction "3_3") (pintype "passive"))
    )
    (net (code "51") (name "Net-(IC1-PA3)") (class "Default")
      (node (ref "IC1") (pin "13") (pinfunction "PA3_13") (pintype "passive"))
      (node (ref "R17") (pin "1") (pinfunction "1_1") (pintype "passive"))
      (node (ref "jst1") (pin "2") (pinfunction "2_2") (pintype "passive"))
    )
    (net (code "52") (name "Net-(IC1-PA4)") (class "Default")
      (node (ref "IC1") (pin "14") (pinfunction "PA4_14") (pintype "passive"))
      (node (ref "R29") (pin "1") (pinfunction "1_1") (pintype "passive"))
      (node (ref "jst1") (pin "1") (pinfunction "1_1") (pintype "passive"))
    )
    (net (code "53") (name "Net-(IC1-PA15)") (class "Default")
      (node (ref "IC1") (pin "38") (pinfunction "PA15_38") (pintype "passive"))
      (node (ref "jst5") (pin "4") (pinfunction "4_4") (pintype "passive"))
    )
    (net (code "54") (name "Net-(IC1-PB3)") (class "Default")
      (node (ref "IC1") (pin "39") (pinfunction "PB3_39") (pintype "passive"))
      (node (ref "jst5") (pin "3") (pinfunction "3_3") (pintype "passive"))
    )
    (net (code "55") (name "Net-(IC1-PB4)") (class "Default")
      (node (ref "IC1") (pin "40") (pinfunction "PB4_40") (pintype "passive"))
      (node (ref "jst5") (pin "2") (pinfunction "2_2") (pintype "passive"))
    )
    (net (code "56") (name "Net-(IC1-PB5)") (class "Default")
      (node (ref "IC1") (pin "41") (pinfunction "PB5_41") (pintype "passive"))
      (node (ref "jst5") (pin "1") (pinfunction "1_1") (pintype "passive"))
    )
    (net (code "57") (name "Net-(IC2-1A)") (class "Default")
      (node (ref "IC2") (pin "2") (pinfunction "1A_2") (pintype "passive"))
      (node (ref "R4") (pin "2") (pinfunction "2_2") (pintype "passive"))
    )
    (net (code "58") (name "Net-(IC2-2A)") (class "Default")
      (node (ref "IC2") (pin "5") (pinfunction "2A_5") (pintype "passive"))
      (node (ref "R6") (pin "2") (pinfunction "2_2") (pintype "passive"))
    )
    (net (code "59") (name "Net-(IC2-3A)") (class "Default")
      (node (ref "IC2") (pin "9") (pinfunction "3A_9") (pintype "passive"))
      (node (ref "R7") (pin "1") (pinfunction "1_1") (pintype "passive"))
    )
    (net (code "60") (name "Net-(IC2-4A)") (class "Default")
      (node (ref "IC2") (pin "12") (pinfunction "4A_12") (pintype "passive"))
      (node (ref "R5") (pin "1") (pinfunction "1_1") (pintype "passive"))
    )
    (net (code "61") (name "Net-(IC3-CANH)") (class "Default")
      (node (ref "IC3") (pin "7") (pinfunction "CANH_7") (pintype "passive"))
      (node (ref "R36") (pin "2") (pinfunction "2_2") (pintype "passive"))
      (node (ref "jst3") (pin "1") (pinfunction "1_1") (pintype "passive"))
    )
    (net (code "62") (name "Net-(IC3-CANL)") (class "Default")
      (node (ref "IC3") (pin "6") (pinfunction "CANL_6") (pintype "passive"))
      (node (ref "R36") (pin "1") (pinfunction "1_1") (pintype "passive"))
      (node (ref "jst3") (pin "2") (pinfunction "2_2") (pintype "passive"))
    )
    (net (code "63") (name "Net-(IC3-RS)") (class "Default")
      (node (ref "IC3") (pin "8") (pinfunction "RS_8") (pintype "passive"))
      (node (ref "R35") (pin "2") (pinfunction "2_2") (pintype "passive"))
    )
    (net (code "64") (name "Net-(IC5-B)") (class "Default")
      (node (ref "IC5") (pin "1") (pinfunction "B_1") (pintype "passive"))
      (node (ref "R22") (pin "2") (pinfunction "2_2") (pintype "passive"))
    )
    (net (code "65") (name "Net-(IC5-C)") (class "Default")
      (node (ref "IC5") (pin "3") (pinfunction "C_3") (pintype "passive"))
      (node (ref "LS1") (pin "2") (pinfunction "-_2") (pintype "passive"))
    )
    (net (code "66") (name "Net-(K1-a1)") (class "Default")
      (node (ref "D1") (pin "2") (pinfunction "2_2") (pintype "passive"))
      (node (ref "K1") (pin "2") (pinfunction "a1_2") (pintype "passive"))
      (node (ref "L1") (pin "1") (pinfunction "5_1") (pintype "passive"))
      (node (ref "R10") (pin "1") (pinfunction "1_1") (pintype "passive"))
    )
    (net (code "67") (name "Net-(K1-a2)") (class "Default")
      (node (ref "D1") (pin "1") (pinfunction "1_1") (pintype "passive"))
      (node (ref "K1") (pin "3") (pinfunction "a2_3") (pintype "passive"))
      (node (ref "Q1") (pin "1") (pinfunction "C_1") (pintype "passive"))
      (node (ref "R11") (pin "1") (pinfunction "1_1") (pintype "passive"))
    )
    (net (code "68") (name "Net-(K2-a1)") (class "Default")
      (node (ref "D4") (pin "2") (pinfunction "2_2") (pintype "passive"))
      (node (ref "K2") (pin "2") (pinfunction "a1_2") (pintype "passive"))
      (node (ref "L4") (pin "1") (pinfunction "5_1") (pintype "passive"))
      (node (ref "R13") (pin "1") (pinfunction "1_1") (pintype "passive"))
    )
    (net (code "69") (name "Net-(K2-a2)") (class "Default")
      (node (ref "D4") (pin "1") (pinfunction "1_1") (pintype "passive"))
      (node (ref "K2") (pin "3") (pinfunction "a2_3") (pintype "passive"))
      (node (ref "Q2") (pin "1") (pinfunction "C_1") (pintype "passive"))
      (node (ref "R14") (pin "1") (pinfunction "1_1") (pintype "passive"))
    )
    (net (code "70") (name "Net-(K3-a1)") (class "Default")
      (node (ref "D5") (pin "2") (pinfunction "2_2") (pintype "passive"))
      (node (ref "K3") (pin "2") (pinfunction "a1_2") (pintype "passive"))
      (node (ref "L5") (pin "1") (pinfunction "5_1") (pintype "passive"))
      (node (ref "R16") (pin "1") (pinfunction "1_1") (pintype "passive"))
    )
    (net (code "71") (name "Net-(K3-a2)") (class "Default")
      (node (ref "D5") (pin "1") (pinfunction "1_1") (pintype "passive"))
      (node (ref "K3") (pin "3") (pinfunction "a2_3") (pintype "passive"))
      (node (ref "Q3") (pin "1") (pinfunction "C_1") (pintype "passive"))
      (node (ref "R18") (pin "1") (pinfunction "1_1") (pintype "passive"))
    )
    (net (code "72") (name "Net-(L1-6)") (class "Default")
      (node (ref "L1") (pin "2") (pinfunction "6_2") (pintype "passive"))
      (node (ref "R11") (pin "2") (pinfunction "2_2") (pintype "passive"))
    )
    (net (code "73") (name "Net-(L4-6)") (class "Default")
      (node (ref "L4") (pin "2") (pinfunction "6_2") (pintype "passive"))
      (node (ref "R14") (pin "2") (pinfunction "2_2") (pintype "passive"))
    )
    (net (code "74") (name "Net-(L5-6)") (class "Default")
      (node (ref "L5") (pin "2") (pinfunction "6_2") (pintype "passive"))
      (node (ref "R18") (pin "2") (pinfunction "2_2") (pintype "passive"))
    )
    (net (code "75") (name "Net-(LED1-A)") (class "Default")
      (node (ref "LED1") (pin "2") (pinfunction "A_2") (pintype "passive"))
      (node (ref "R24") (pin "2") (pinfunction "2_2") (pintype "passive"))
    )
    (net (code "76") (name "Net-(LED2-A)") (class "Default")
      (node (ref "LED2") (pin "2") (pinfunction "A_2") (pintype "passive"))
      (node (ref "R21") (pin "2") (pinfunction "2_2") (pintype "passive"))
    )
    (net (code "77") (name "Net-(M1-RXD)") (class "Default")
      (node (ref "M1") (pin "5") (pinfunction "RXD_5") (pintype "passive"))
      (node (ref "R1") (pin "2") (pinfunction "2_2") (pintype "passive"))
      (node (ref "R2") (pin "2") (pinfunction "2_2") (pintype "passive"))
    )
    (net (code "78") (name "Net-(Q1-B)") (class "Default")
      (node (ref "Q1") (pin "2") (pinfunction "B_2") (pintype "passive"))
      (node (ref "R12") (pin "1") (pinfunction "1_1") (pintype "passive"))
    )
    (net (code "79") (name "Net-(Q2-B)") (class "Default")
      (node (ref "Q2") (pin "2") (pinfunction "B_2") (pintype "passive"))
      (node (ref "R15") (pin "1") (pinfunction "1_1") (pintype "passive"))
    )
    (net (code "80") (name "Net-(Q3-B)") (class "Default")
      (node (ref "Q3") (pin "2") (pinfunction "B_2") (pintype "passive"))
      (node (ref "R19") (pin "1") (pinfunction "1_1") (pintype "passive"))
    )
    (net (code "81") (name "unconnected-(B1-Pad1)") (class "Default")
      (node (ref "B1") (pin "1") (pinfunction "1_1") (pintype "passive"))
    )
    (net (code "82") (name "unconnected-(B1-Pad2)") (class "Default")
      (node (ref "B1") (pin "2") (pinfunction "2_2") (pintype "passive"))
    )
    (net (code "83") (name "unconnected-(IC3-VREF-Pad5)") (class "Default")
      (node (ref "IC3") (pin "5") (pinfunction "VREF_5") (pintype "passive"))
    )
    (net (code "84") (name "unconnected-(J2-DAT1-Pad8)") (class "Default")
      (node (ref "J2") (pin "8") (pinfunction "DAT1_8") (pintype "passive"))
    )
    (net (code "85") (name "unconnected-(J2-DAT2-Pad1)") (class "Default")
      (node (ref "J2") (pin "1") (pinfunction "DAT2_1") (pintype "passive"))
    )
    (net (code "86") (name "unconnected-(J2-DETECT_NAIL-Pad9)") (class "Default")
      (node (ref "J2") (pin "9") (pinfunction "DETECT_NAIL_9") (pintype "passive"))
    )
    (net (code "87") (name "unconnected-(J2-SWITCH_NAIL-Pad10)") (class "Default")
      (node (ref "J2") (pin "10") (pinfunction "SWITCH_NAIL_10") (pintype "passive"))
    )
    (net (code "88") (name "unconnected-(J10-Pad2)") (class "Default")
      (node (ref "J10") (pin "2") (pinfunction "2_2") (pintype "passive"))
    )
    (net (code "89") (name "unconnected-(M1-AUX-Pad3)") (class "Default")
      (node (ref "M1") (pin "3") (pinfunction "AUX_3") (pintype "passive"))
    )
  )
)
